# 5V_buck.net
KiCad netlist of a schematic drawn in Altium Designer
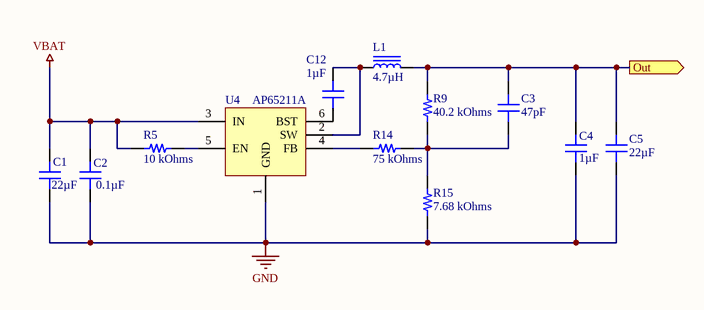
[diagram p0: 5V_buck.SchDoc]

(export (version "E")
  (design (tool "Eeschema 10.0.6"))
  (components
    (comp (ref "C1")
      (value "22µF")
      (footprint "CAP 0805_2012")
      (description "CAP CER 10UF 25V X7S 0805")
      (fields
        (field (name "PART NUMBER") "C2012X7S1E106K125AC")
        (field (name "MANUFACTURER") "TDK Corporation")
      )
      (libsource (lib "Celestial Altium Library - altium_library") (part "Capacitor"))
    )
    (comp (ref "C2")
      (value "0.1µF")
      (footprint "CAP 0603_1608")
      (description "CAP CER 0.1UF 100V 0603 EPOXY")
      (fields
        (field (name "PART NUMBER") "GCG188R92A104KA03D")
        (field (name "MANUFACTURER") "Murata Electronics")
      )
      (libsource (lib "Celestial Altium Library - altium_library") (part "Capacitor"))
    )
    (comp (ref "C3")
      (value "47pF")
      (footprint "CAP 0603_1608")
      (description "CAP CER 47PF 100V NP0 0603")
      (fields
        (field (name "PART NUMBER") "C1608NP02A470J080AA")
        (field (name "MANUFACTURER") "TDK Corporation")
      )
      (libsource (lib "Celestial Altium Library - altium_library") (part "Capacitor"))
    )
    (comp (ref "C4")
      (value "1µF")
      (footprint "CAP 0603_1608")
      (description "CAP CER 1UF 25V X7R 0603")
      (fields
        (field (name "PART NUMBER") "GCJ188R71E105KA01D")
        (field (name "MANUFACTURER") "Murata Electronics")
      )
      (libsource (lib "Celestial Altium Library - altium_library") (part "Capacitor"))
    )
    (comp (ref "C5")
      (value "22µF")
      (footprint "CAP 0805_2012")
      (description "CAP CER 22UF 16V X5R 0805")
      (fields
        (field (name "PART NUMBER") "CL21A226MOQNNNE")
        (field (name "MANUFACTURER") "Samsung Electro-Mechanics")
      )
      (libsource (lib "Celestial Altium Library - altium_library") (part "Capacitor"))
    )
    (comp (ref "C12")
      (value "1µF")
      (footprint "CAP 0603_1608")
      (description "CAP CER 1UF 25V X7R 0603")
      (fields
        (field (name "PART NUMBER") "GCJ188R71E105KA01D")
        (field (name "MANUFACTURER") "Murata Electronics")
      )
      (libsource (lib "Celestial Altium Library - altium_library") (part "Capacitor"))
    )
    (comp (ref "L1")
      (value "4.7µH")
      (footprint "IND 1008_2520")
      (description "FIXED IND 4.7UH 1A 110 MOHM SMD")
      (fields (field (name "PART NUMBER") "MLP2520S4R7ST0S1") (field (name "MANUFACTURER") "TDK Corporation"))
      (libsource (lib "Celestial Altium Library - altium_library") (part "Inductor"))
    )
    (comp (ref "R5")
      (value "10 kOhms")
      (footprint "RES 0603_1608")
      (description "RES 10K OHM 0.1% 1/16W 0603")
      (fields
        (field (name "PART NUMBER") "RNCS0603BKE10K0")
        (field (name "MANUFACTURER") "Stackpole Electronics Inc")
      )
      (libsource (lib "Celestial Altium Library - altium_library") (part "Resistor"))
    )
    (comp (ref "R9")
      (value "40.2 kOhms")
      (footprint "RES 0603_1608")
      (description "RES SMD 40.2KOHM 0.5% 1/10W 0603")
      (fields (field (name "PART NUMBER") "RT0603DRD0740K2L") (field (name "MANUFACTURER") "Yageo"))
      (libsource (lib "Celestial Altium Library - altium_library") (part "Resistor"))
    )
    (comp (ref "R14")
      (value "75 kOhms")
      (footprint "RES 0603_1608")
      (description "RES SMD 75K OHM 5% 1/10W 0603")
      (fields (field (name "PART NUMBER") "CR0603-JW-753ELF") (field (name "MANUFACTURER") "Bourns Inc."))
      (libsource (lib "Celestial Altium Library - altium_library") (part "Resistor"))
    )
    (comp (ref "R15")
      (value "7.68 kOhms")
      (footprint "RES 0603_1608")
      (description "RES 7.68K OHM 1% 1/10W 0603")
      (fields
        (field (name "PART NUMBER") "RMCF0603FT7K68")
        (field (name "MANUFACTURER") "Stackpole Electronics Inc")
      )
      (libsource (lib "Celestial Altium Library - altium_library") (part "Resistor"))
    )
    (comp (ref "U4")
      (value "AP65211A")
      (footprint "TSOT-26-6")
      (description "ADJ step down Buck")
      (libsource (lib "IC") (part "AP65211A"))
    )
  )
  (nets
    (net (code "1") (name "/Out") (class "Default")
      (node (ref "C3") (pin "2") (pinfunction "2_2") (pintype "passive"))
      (node (ref "C4") (pin "2") (pinfunction "2_2") (pintype "passive"))
      (node (ref "C5") (pin "2") (pinfunction "2_2") (pintype "passive"))
      (node (ref "L1") (pin "2") (pinfunction "2_2") (pintype "passive"))
      (node (ref "R9") (pin "2") (pinfunction "2_2") (pintype "passive"))
    )
    (net (code "2") (name "GND") (class "Default")
      (node (ref "C1") (pin "1") (pinfunction "1_1") (pintype "passive"))
      (node (ref "C2") (pin "2") (pinfunction "2_2") (pintype "passive"))
      (node (ref "C4") (pin "1") (pinfunction "1_1") (pintype "passive"))
      (node (ref "C5") (pin "1") (pinfunction "1_1") (pintype "passive"))
      (node (ref "R15") (pin "1") (pinfunction "1_1") (pintype "passive"))
      (node (ref "U4") (pin "1") (pinfunction "GND_1") (pintype "passive"))
    )
    (net (code "3") (name "Net-(C3-Pad1)") (class "Default")
      (node (ref "C3") (pin "1") (pinfunction "1_1") (pintype "passive"))
      (node (ref "R14") (pin "2") (pinfunction "2_2") (pintype "passive"))
      (node (ref "R15") (pin "2") (pinfunction "2_2") (pintype "passive"))
      (node (ref "R9") (pin "1") (pinfunction "1_1") (pintype "passive"))
    )
    (net (code "4") (name "Net-(U4-BST)") (class "Default")
      (node (ref "C12") (pin "2") (pinfunction "2_2") (pintype "passive"))
      (node (ref "U4") (pin "6") (pinfunction "BST_6") (pintype "passive"))
    )
    (net (code "5") (name "Net-(U4-EN)") (class "Default")
      (node (ref "R5") (pin "1") (pinfunction "1_1") (pintype "passive"))
      (node (ref "U4") (pin "5") (pinfunction "EN_5") (pintype "passive"))
    )
    (net (code "6") (name "Net-(U4-FB)") (class "Default")
      (node (ref "R14") (pin "1") (pinfunction "1_1") (pintype "passive"))
      (node (ref "U4") (pin "4") (pinfunction "FB_4") (pintype "passive"))
    )
    (net (code "7") (name "Net-(U4-SW)") (class "Default")
      (node (ref "C12") (pin "1") (pinfunction "1_1") (pintype "passive"))
      (node (ref "L1") (pin "1") (pinfunction "1_1") (pintype "passive"))
      (node (ref "U4") (pin "2") (pinfunction "SW_2") (pintype "passive"))
    )
    (net (code "8") (name "VBAT") (class "Default")
      (node (ref "C1") (pin "2") (pinfunction "2_2") (pintype "passive"))
      (node (ref "C2") (pin "1") (pinfunction "1_1") (pintype "passive"))
      (node (ref "R5") (pin "2") (pinfunction "2_2") (pintype "passive"))
      (node (ref "U4") (pin "3") (pinfunction "IN_3") (pintype "passive"))
    )
  )
)
